# ATmega128.net
KiCad netlist of a schematic drawn in Altium Designer
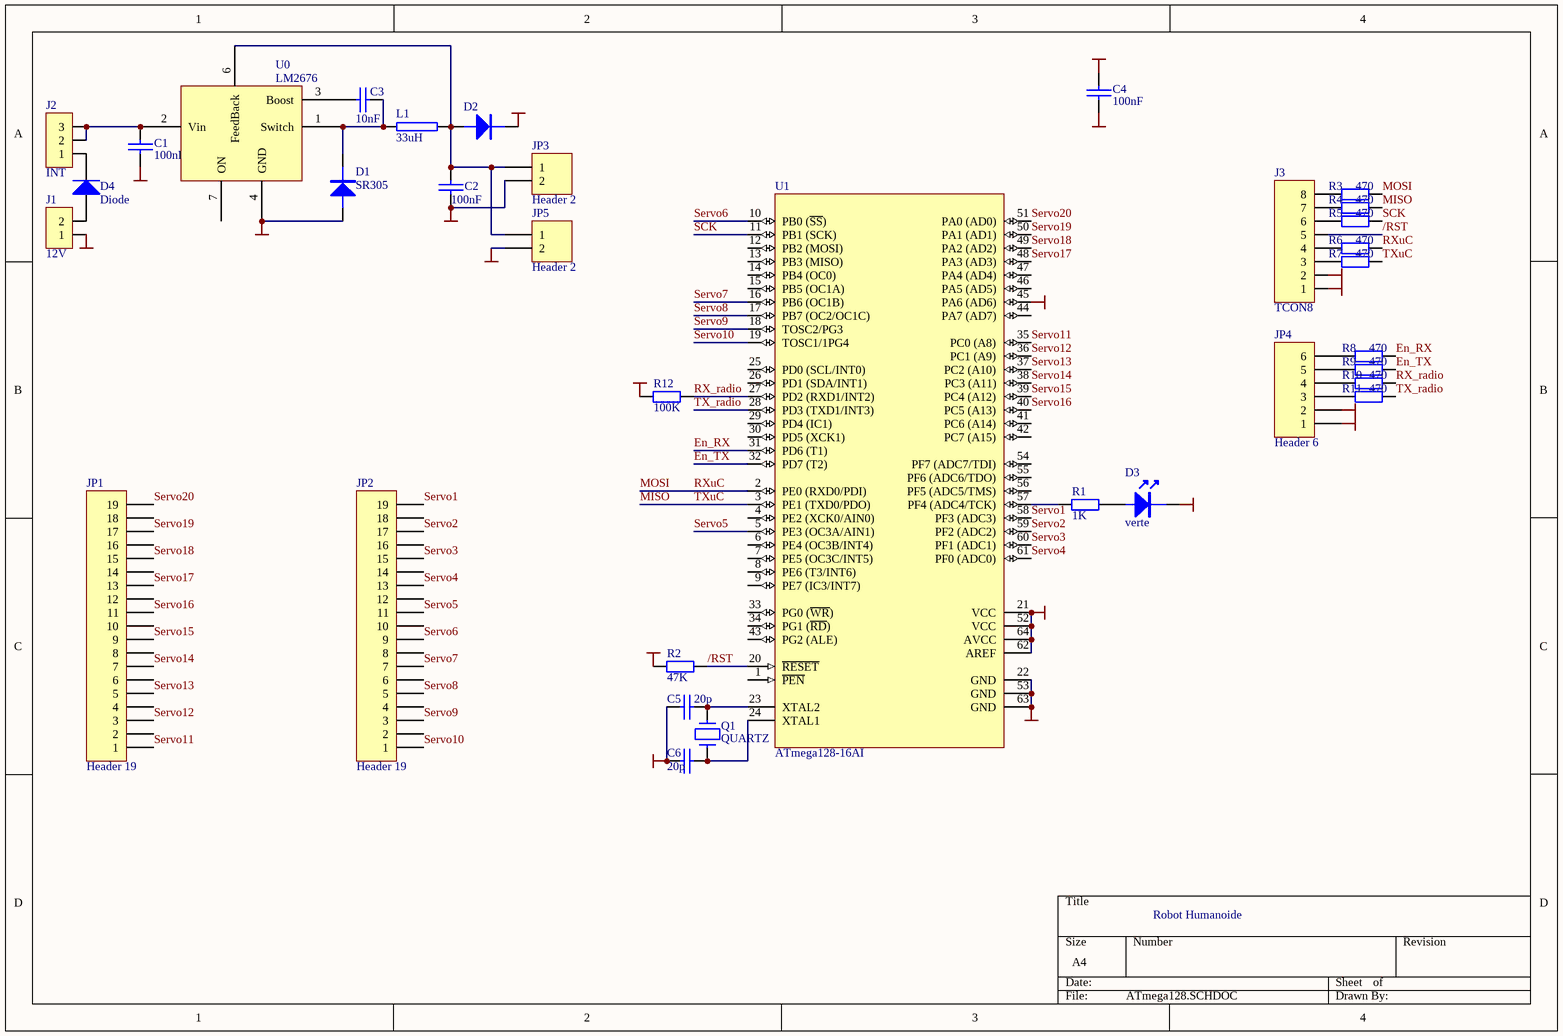
[diagram p0: ATmega128.SCHDOC]

(export (version "E")
  (design (tool "Eeschema 10.0.6"))
  (components
    (comp (ref "C1") (value "100nF") (footprint "0805") (libsource (lib "*") (part "CAP")))
    (comp (ref "C2") (value "100nF") (footprint "0805") (libsource (lib "*") (part "CAP")))
    (comp (ref "C3") (value "10nF") (footprint "0805") (libsource (lib "*") (part "CONDO")))
    (comp (ref "C4") (value "100nF") (footprint "0805") (libsource (lib "*") (part "CAP")))
    (comp (ref "C5") (value "20p") (footprint "0805") (libsource (lib "*") (part "CONDO")))
    (comp (ref "C6") (value "20p") (footprint "0805") (libsource (lib "*") (part "CONDO")))
    (comp (ref "D1") (value "SR305") (footprint "1812") (libsource (lib "*") (part "DIODE")))
    (comp (ref "D2") (value "~") (footprint "1812") (libsource (lib "*") (part "DIODE")))
    (comp (ref "D3") (value "verte") (footprint "0603") (libsource (lib "*") (part "LED")))
    (comp (ref "D4")
      (value "Diode")
      (footprint "DSO-C2/X3.3")
      (description "Default Diode")
      (fields (field (name "PUBLISHER") "Altium Limited"))
      (libsource (lib "Miscellaneous Devices") (part "Diode"))
    )
    (comp (ref "J1") (value "12V") (footprint "CON2") (libsource (lib "*") (part "CON2")))
    (comp (ref "J2") (value "INT") (footprint "TSIP3") (libsource (lib "*") (part "TCON3")))
    (comp (ref "J3") (value "TCON8") (footprint "TSIP8") (libsource (lib "ROB04") (part "TCON8")))
    (comp (ref "JP1")
      (value "Header 19")
      (footprint "HDR1X19")
      (description "Header, 19-Pin")
      (fields (field (name "PUBLISHER") "Altium Limited"))
      (libsource (lib "Miscellaneous Connectors") (part "Header 19"))
    )
    (comp (ref "JP2")
      (value "Header 19")
      (footprint "HDR1X19")
      (description "Header, 19-Pin")
      (fields (field (name "PUBLISHER") "Altium Limited"))
      (libsource (lib "Miscellaneous Connectors") (part "Header 19"))
    )
    (comp (ref "JP3")
      (value "Header 2")
      (footprint "HDR1X2")
      (description "Header, 2-Pin")
      (fields (field (name "PUBLISHER") "Altium Limited"))
      (libsource (lib "Miscellaneous Connectors") (part "Header 2"))
    )
    (comp (ref "JP4")
      (value "Header 6")
      (footprint "TSIP6")
      (description "Header, 6-Pin")
      (fields (field (name "PUBLISHER") "Altium Limited"))
      (libsource (lib "Miscellaneous Connectors") (part "Header 6"))
    )
    (comp (ref "JP5")
      (value "Header 2")
      (footprint "HDR1X2")
      (description "Header, 2-Pin")
      (fields (field (name "PUBLISHER") "Altium Limited"))
      (libsource (lib "Miscellaneous Connectors") (part "Header 2"))
    )
    (comp (ref "L1")
      (value "33uH")
      (footprint "TRES")
      (fields (field (name "PUBLISHER") "*"))
      (libsource (lib "*") (part "RES2"))
    )
    (comp (ref "Q1") (value "QUARTZ") (footprint "XTAL1") (libsource (lib "*") (part "QUARTZ")))
    (comp (ref "R1")
      (value "1K")
      (footprint "0805")
      (description "Resistor")
      (fields (field (name "Comment") "Res2") (field (name "PUBLISHER") "Altium Limited"))
      (libsource (lib "") (part "Res2_1"))
    )
    (comp (ref "R2")
      (value "47K")
      (footprint "0805")
      (description "Resistor")
      (fields (field (name "Comment") "Res2") (field (name "PUBLISHER") "Altium Limited"))
      (libsource (lib "") (part "Res2_1"))
    )
    (comp (ref "R3")
      (value "470")
      (footprint "0805")
      (description "Resistor")
      (fields (field (name "Comment") "Res2") (field (name "PUBLISHER") "Altium Limited"))
      (libsource (lib "Miscellaneous Devices") (part "Res2"))
    )
    (comp (ref "R4")
      (value "470")
      (footprint "0805")
      (description "Resistor")
      (fields (field (name "Comment") "Res2") (field (name "PUBLISHER") "Altium Limited"))
      (libsource (lib "Miscellaneous Devices") (part "Res2"))
    )
    (comp (ref "R5")
      (value "470")
      (footprint "0805")
      (description "Resistor")
      (fields (field (name "Comment") "Res2") (field (name "PUBLISHER") "Altium Limited"))
      (libsource (lib "Miscellaneous Devices") (part "Res2"))
    )
    (comp (ref "R6")
      (value "470")
      (footprint "0805")
      (description "Resistor")
      (fields (field (name "Comment") "Res2") (field (name "PUBLISHER") "Altium Limited"))
      (libsource (lib "Miscellaneous Devices") (part "Res2"))
    )
    (comp (ref "R7")
      (value "470")
      (footprint "0805")
      (description "Resistor")
      (fields (field (name "Comment") "Res2") (field (name "PUBLISHER") "Altium Limited"))
      (libsource (lib "Miscellaneous Devices") (part "Res2"))
    )
    (comp (ref "R8")
      (value "470")
      (footprint "0805")
      (description "Resistor")
      (fields (field (name "Comment") "Res2") (field (name "PUBLISHER") "Altium Limited"))
      (libsource (lib "Miscellaneous Devices") (part "Res2"))
    )
    (comp (ref "R9")
      (value "470")
      (footprint "0805")
      (description "Resistor")
      (fields (field (name "Comment") "Res2") (field (name "PUBLISHER") "Altium Limited"))
      (libsource (lib "Miscellaneous Devices") (part "Res2"))
    )
    (comp (ref "R10")
      (value "470")
      (footprint "0805")
      (description "Resistor")
      (fields (field (name "Comment") "Res2") (field (name "PUBLISHER") "Altium Limited"))
      (libsource (lib "Miscellaneous Devices") (part "Res2"))
    )
    (comp (ref "R11")
      (value "470")
      (footprint "0805")
      (description "Resistor")
      (fields (field (name "Comment") "Res2") (field (name "PUBLISHER") "Altium Limited"))
      (libsource (lib "Miscellaneous Devices") (part "Res2"))
    )
    (comp (ref "R12")
      (value "100K")
      (footprint "0805")
      (description "Resistor")
      (fields (field (name "Comment") "Res2") (field (name "PUBLISHER") "Altium Limited"))
      (libsource (lib "") (part "Res2_1"))
    )
    (comp (ref "U0") (value "LM2676") (footprint "LM2676") (libsource (lib "*") (part "LM2676")))
    (comp (ref "U1")
      (value "ATmega128-16AI")
      (footprint "64A")
      (description "8-Bit AVR Microcontroller with 128K Bytes of In-System Programmable Flash Memory")
      (fields (field (name "PUBLISHER") "Altium Limited"))
      (libsource (lib "Atmel Microcontroller 8-Bit AVR") (part "ATmega128-16AI"))
    )
  )
  (nets
    (net (code "1") (name "/En_RX") (class "Default")
      (node (ref "R8") (pin "2") (pinfunction "2_2") (pintype "passive"))
      (node (ref "U1") (pin "31") (pinfunction "PD6_(T1)_31") (pintype "bidirectional"))
    )
    (net (code "2") (name "/En_TX") (class "Default")
      (node (ref "R9") (pin "2") (pinfunction "2_2") (pintype "passive"))
      (node (ref "U1") (pin "32") (pinfunction "PD7_(T2)_32") (pintype "bidirectional"))
    )
    (net (code "3") (name "/MISO") (class "Default")
      (node (ref "R4") (pin "2") (pinfunction "2_2") (pintype "passive"))
      (node (ref "R7") (pin "2") (pinfunction "2_2") (pintype "passive"))
      (node (ref "U1") (pin "3") (pinfunction "PE1_(TXD0/PDO)_3") (pintype "bidirectional"))
    )
    (net (code "4") (name "/MOSI") (class "Default")
      (node (ref "R3") (pin "2") (pinfunction "2_2") (pintype "passive"))
      (node (ref "R6") (pin "2") (pinfunction "2_2") (pintype "passive"))
      (node (ref "U1") (pin "2") (pinfunction "PE0_(RXD0/PDI)_2") (pintype "bidirectional"))
    )
    (net (code "5") (name "/RX_radio") (class "Default")
      (node (ref "R10") (pin "2") (pinfunction "2_2") (pintype "passive"))
      (node (ref "R12") (pin "1") (pinfunction "1_1") (pintype "passive"))
      (node (ref "U1") (pin "27") (pinfunction "PD2_(RXD1/INT2)_27") (pintype "bidirectional"))
    )
    (net (code "6") (name "/SCK") (class "Default")
      (node (ref "R5") (pin "2") (pinfunction "2_2") (pintype "passive"))
      (node (ref "U1") (pin "11") (pinfunction "PB1_(SCK)_11") (pintype "bidirectional"))
    )
    (net (code "7") (name "/Servo1") (class "Default")
      (node (ref "JP2") (pin "19") (pinfunction "19_19") (pintype "passive"))
      (node (ref "U1") (pin "58") (pinfunction "PF3_(ADC3)_58") (pintype "bidirectional"))
    )
    (net (code "8") (name "/Servo2") (class "Default")
      (node (ref "JP2") (pin "17") (pinfunction "17_17") (pintype "passive"))
      (node (ref "U1") (pin "59") (pinfunction "PF2_(ADC2)_59") (pintype "bidirectional"))
    )
    (net (code "9") (name "/Servo3") (class "Default")
      (node (ref "JP2") (pin "15") (pinfunction "15_15") (pintype "passive"))
      (node (ref "U1") (pin "60") (pinfunction "PF1_(ADC1)_60") (pintype "bidirectional"))
    )
    (net (code "10") (name "/Servo4") (class "Default")
      (node (ref "JP2") (pin "13") (pinfunction "13_13") (pintype "passive"))
      (node (ref "U1") (pin "61") (pinfunction "PF0_(ADC0)_61") (pintype "bidirectional"))
    )
    (net (code "11") (name "/Servo5") (class "Default")
      (node (ref "JP2") (pin "11") (pinfunction "11_11") (pintype "passive"))
      (node (ref "U1") (pin "5") (pinfunction "PE3_(OC3A/AIN1)_5") (pintype "bidirectional"))
    )
    (net (code "12") (name "/Servo6") (class "Default")
      (node (ref "JP2") (pin "9") (pinfunction "9_9") (pintype "passive"))
      (node (ref "U1") (pin "10") (pinfunction "PB0_(~{SS})_10") (pintype "bidirectional"))
    )
    (net (code "13") (name "/Servo7") (class "Default")
      (node (ref "JP2") (pin "7") (pinfunction "7_7") (pintype "passive"))
      (node (ref "U1") (pin "16") (pinfunction "PB6_(OC1B)_16") (pintype "bidirectional"))
    )
    (net (code "14") (name "/Servo8") (class "Default")
      (node (ref "JP2") (pin "5") (pinfunction "5_5") (pintype "passive"))
      (node (ref "U1") (pin "17") (pinfunction "PB7_(OC2/OC1C)_17") (pintype "bidirectional"))
    )
    (net (code "15") (name "/Servo9") (class "Default")
      (node (ref "JP2") (pin "3") (pinfunction "3_3") (pintype "passive"))
      (node (ref "U1") (pin "18") (pinfunction "TOSC2/PG3_18") (pintype "bidirectional"))
    )
    (net (code "16") (name "/Servo10") (class "Default")
      (node (ref "JP2") (pin "1") (pinfunction "1_1") (pintype "passive"))
      (node (ref "U1") (pin "19") (pinfunction "TOSC1/1PG4_19") (pintype "bidirectional"))
    )
    (net (code "17") (name "/Servo11") (class "Default")
      (node (ref "JP1") (pin "1") (pinfunction "1_1") (pintype "passive"))
      (node (ref "U1") (pin "35") (pinfunction "PC0_(A8)_35") (pintype "bidirectional"))
    )
    (net (code "18") (name "/Servo12") (class "Default")
      (node (ref "JP1") (pin "3") (pinfunction "3_3") (pintype "passive"))
      (node (ref "U1") (pin "36") (pinfunction "PC1_(A9)_36") (pintype "bidirectional"))
    )
    (net (code "19") (name "/Servo13") (class "Default")
      (node (ref "JP1") (pin "5") (pinfunction "5_5") (pintype "passive"))
      (node (ref "U1") (pin "37") (pinfunction "PC2_(A10)_37") (pintype "bidirectional"))
    )
    (net (code "20") (name "/Servo14") (class "Default")
      (node (ref "JP1") (pin "7") (pinfunction "7_7") (pintype "passive"))
      (node (ref "U1") (pin "38") (pinfunction "PC3_(A11)_38") (pintype "bidirectional"))
    )
    (net (code "21") (name "/Servo15") (class "Default")
      (node (ref "JP1") (pin "9") (pinfunction "9_9") (pintype "passive"))
      (node (ref "U1") (pin "39") (pinfunction "PC4_(A12)_39") (pintype "bidirectional"))
    )
    (net (code "22") (name "/Servo16") (class "Default")
      (node (ref "JP1") (pin "11") (pinfunction "11_11") (pintype "passive"))
      (node (ref "U1") (pin "40") (pinfunction "PC5_(A13)_40") (pintype "bidirectional"))
    )
    (net (code "23") (name "/Servo17") (class "Default")
      (node (ref "JP1") (pin "13") (pinfunction "13_13") (pintype "passive"))
      (node (ref "U1") (pin "48") (pinfunction "PA3_(AD3)_48") (pintype "bidirectional"))
    )
    (net (code "24") (name "/Servo18") (class "Default")
      (node (ref "JP1") (pin "15") (pinfunction "15_15") (pintype "passive"))
      (node (ref "U1") (pin "49") (pinfunction "PA2_(AD2)_49") (pintype "bidirectional"))
    )
    (net (code "25") (name "/Servo19") (class "Default")
      (node (ref "JP1") (pin "17") (pinfunction "17_17") (pintype "passive"))
      (node (ref "U1") (pin "50") (pinfunction "PA1_(AD1)_50") (pintype "bidirectional"))
    )
    (net (code "26") (name "/Servo20") (class "Default")
      (node (ref "JP1") (pin "19") (pinfunction "19_19") (pintype "passive"))
      (node (ref "U1") (pin "51") (pinfunction "PA0_(AD0)_51") (pintype "bidirectional"))
    )
    (net (code "27") (name "/TX_radio") (class "Default")
      (node (ref "R11") (pin "2") (pinfunction "2_2") (pintype "passive"))
      (node (ref "U1") (pin "28") (pinfunction "PD3_(TXD1/INT3)_28") (pintype "bidirectional"))
    )
    (net (code "28") (name "/{slash}RST") (class "Default")
      (node (ref "J3") (pin "5") (pinfunction "5_5") (pintype "passive"))
      (node (ref "R2") (pin "1") (pinfunction "1_1") (pintype "passive"))
      (node (ref "U1") (pin "20") (pinfunction "~{RESET}_20") (pintype "input"))
    )
    (net (code "29") (name "5V") (class "Default")
      (node (ref "C4") (pin "2") (pintype "passive"))
      (node (ref "D2") (pin "1") (pintype "passive"))
      (node (ref "J3") (pin "1") (pinfunction "1_1") (pintype "passive"))
      (node (ref "JP4") (pin "1") (pinfunction "1_1") (pintype "passive"))
      (node (ref "R12") (pin "2") (pinfunction "2_2") (pintype "passive"))
      (node (ref "R2") (pin "2") (pinfunction "2_2") (pintype "passive"))
      (node (ref "U1") (pin "21") (pinfunction "VCC_21") (pintype "power_in"))
      (node (ref "U1") (pin "52") (pinfunction "VCC_52") (pintype "power_in"))
      (node (ref "U1") (pin "62") (pinfunction "AREF_62") (pintype "passive"))
      (node (ref "U1") (pin "64") (pinfunction "AVCC_64") (pintype "power_in"))
    )
    (net (code "30") (name "GND") (class "Default")
      (node (ref "C1") (pin "1") (pintype "passive"))
      (node (ref "C2") (pin "1") (pintype "passive"))
      (node (ref "C4") (pin "1") (pintype "passive"))
      (node (ref "C5") (pin "2") (pintype "passive"))
      (node (ref "C6") (pin "2") (pintype "passive"))
      (node (ref "D1") (pin "2") (pintype "passive"))
      (node (ref "D3") (pin "2") (pintype "passive"))
      (node (ref "J1") (pin "1") (pinfunction "1_1") (pintype "passive"))
      (node (ref "J3") (pin "2") (pinfunction "2_2") (pintype "passive"))
      (node (ref "JP3") (pin "2") (pinfunction "2_2") (pintype "passive"))
      (node (ref "JP4") (pin "2") (pinfunction "2_2") (pintype "passive"))
      (node (ref "JP5") (pin "2") (pinfunction "2_2") (pintype "passive"))
      (node (ref "U0") (pin "4") (pinfunction "GND_4") (pintype "passive"))
      (node (ref "U1") (pin "22") (pinfunction "GND_22") (pintype "power_in"))
      (node (ref "U1") (pin "45") (pinfunction "PA6_(AD6)_45") (pintype "bidirectional"))
      (node (ref "U1") (pin "53") (pinfunction "GND_53") (pintype "power_in"))
      (node (ref "U1") (pin "63") (pinfunction "GND_63") (pintype "power_in"))
    )
    (net (code "31") (name "Net-(D3-Pad1)") (class "Default")
      (node (ref "D3") (pin "1") (pintype "passive"))
      (node (ref "R1") (pin "1") (pinfunction "1_1") (pintype "passive"))
    )
    (net (code "32") (name "Net-(D4-A)") (class "Default")
      (node (ref "D4") (pin "1") (pinfunction "A_1") (pintype "passive"))
      (node (ref "J1") (pin "2") (pinfunction "2_2") (pintype "passive"))
    )
    (net (code "33") (name "Net-(D4-K)") (class "Default")
      (node (ref "D4") (pin "2") (pinfunction "K_2") (pintype "passive"))
      (node (ref "J2") (pin "1") (pinfunction "1_1") (pintype "passive"))
    )
    (net (code "34") (name "Net-(J3-Pad3)") (class "Default")
      (node (ref "J3") (pin "3") (pinfunction "3_3") (pintype "passive"))
      (node (ref "R7") (pin "1") (pinfunction "1_1") (pintype "passive"))
    )
    (net (code "35") (name "Net-(J3-Pad4)") (class "Default")
      (node (ref "J3") (pin "4") (pinfunction "4_4") (pintype "passive"))
      (node (ref "R6") (pin "1") (pinfunction "1_1") (pintype "passive"))
    )
    (net (code "36") (name "Net-(J3-Pad6)") (class "Default")
      (node (ref "J3") (pin "6") (pinfunction "6_6") (pintype "passive"))
      (node (ref "R5") (pin "1") (pinfunction "1_1") (pintype "passive"))
    )
    (net (code "37") (name "Net-(J3-Pad7)") (class "Default")
      (node (ref "J3") (pin "7") (pinfunction "7_7") (pintype "passive"))
      (node (ref "R4") (pin "1") (pinfunction "1_1") (pintype "passive"))
    )
    (net (code "38") (name "Net-(J3-Pad8)") (class "Default")
      (node (ref "J3") (pin "8") (pinfunction "8_8") (pintype "passive"))
      (node (ref "R3") (pin "1") (pinfunction "1_1") (pintype "passive"))
    )
    (net (code "39") (name "Net-(JP4-Pad3)") (class "Default")
      (node (ref "JP4") (pin "3") (pinfunction "3_3") (pintype "passive"))
      (node (ref "R11") (pin "1") (pinfunction "1_1") (pintype "passive"))
    )
    (net (code "40") (name "Net-(JP4-Pad4)") (class "Default")
      (node (ref "JP4") (pin "4") (pinfunction "4_4") (pintype "passive"))
      (node (ref "R10") (pin "1") (pinfunction "1_1") (pintype "passive"))
    )
    (net (code "41") (name "Net-(JP4-Pad5)") (class "Default")
      (node (ref "JP4") (pin "5") (pinfunction "5_5") (pintype "passive"))
      (node (ref "R9") (pin "1") (pinfunction "1_1") (pintype "passive"))
    )
    (net (code "42") (name "Net-(JP4-Pad6)") (class "Default")
      (node (ref "JP4") (pin "6") (pinfunction "6_6") (pintype "passive"))
      (node (ref "R8") (pin "1") (pinfunction "1_1") (pintype "passive"))
    )
    (net (code "43") (name "Net-(U0-Boost)") (class "Default")
      (node (ref "C3") (pin "1") (pintype "passive"))
      (node (ref "U0") (pin "3") (pinfunction "Boost_3") (pintype "passive"))
    )
    (net (code "44") (name "Net-(U0-FeedBack)") (class "Default")
      (node (ref "C2") (pin "2") (pintype "passive"))
      (node (ref "D2") (pin "2") (pintype "passive"))
      (node (ref "JP3") (pin "1") (pinfunction "1_1") (pintype "passive"))
      (node (ref "JP5") (pin "1") (pinfunction "1_1") (pintype "passive"))
      (node (ref "L1") (pin "2") (pintype "passive"))
      (node (ref "U0") (pin "6") (pinfunction "FeedBack_6") (pintype "passive"))
    )
    (net (code "45") (name "Net-(U0-Switch)") (class "Default")
      (node (ref "C3") (pin "2") (pintype "passive"))
      (node (ref "D1") (pin "1") (pintype "passive"))
      (node (ref "L1") (pin "1") (pintype "passive"))
      (node (ref "U0") (pin "1") (pinfunction "Switch_1") (pintype "passive"))
    )
    (net (code "46") (name "Net-(U0-Vin)") (class "Default")
      (node (ref "C1") (pin "2") (pintype "passive"))
      (node (ref "J2") (pin "2") (pinfunction "2_2") (pintype "passive"))
      (node (ref "J2") (pin "3") (pinfunction "3_3") (pintype "passive"))
      (node (ref "U0") (pin "2") (pinfunction "Vin_2") (pintype "passive"))
    )
    (net (code "47") (name "Net-(U1-PF4_(ADC4{slash}TCK))") (class "Default")
      (node (ref "R1") (pin "2") (pinfunction "2_2") (pintype "passive"))
      (node (ref "U1") (pin "57") (pinfunction "PF4_(ADC4/TCK)_57") (pintype "bidirectional"))
    )
    (net (code "48") (name "Net-(U1-XTAL1)") (class "Default")
      (node (ref "C6") (pin "1") (pintype "passive"))
      (node (ref "Q1") (pin "2") (pintype "passive"))
      (node (ref "U1") (pin "24") (pinfunction "XTAL1_24") (pintype "passive"))
    )
    (net (code "49") (name "Net-(U1-XTAL2)") (class "Default")
      (node (ref "C5") (pin "1") (pintype "passive"))
      (node (ref "Q1") (pin "1") (pintype "passive"))
      (node (ref "U1") (pin "23") (pinfunction "XTAL2_23") (pintype "passive"))
    )
    (net (code "50") (name "unconnected-(JP1-Pad2)") (class "Default")
      (node (ref "JP1") (pin "2") (pinfunction "2_2") (pintype "passive"))
    )
    (net (code "51") (name "unconnected-(JP1-Pad4)") (class "Default")
      (node (ref "JP1") (pin "4") (pinfunction "4_4") (pintype "passive"))
    )
    (net (code "52") (name "unconnected-(JP1-Pad6)") (class "Default")
      (node (ref "JP1") (pin "6") (pinfunction "6_6") (pintype "passive"))
    )
    (net (code "53") (name "unconnected-(JP1-Pad8)") (class "Default")
      (node (ref "JP1") (pin "8") (pinfunction "8_8") (pintype "passive"))
    )
    (net (code "54") (name "unconnected-(JP1-Pad10)") (class "Default")
      (node (ref "JP1") (pin "10") (pinfunction "10_10") (pintype "passive"))
    )
    (net (code "55") (name "unconnected-(JP1-Pad12)") (class "Default")
      (node (ref "JP1") (pin "12") (pinfunction "12_12") (pintype "passive"))
    )
    (net (code "56") (name "unconnected-(JP1-Pad14)") (class "Default")
      (node (ref "JP1") (pin "14") (pinfunction "14_14") (pintype "passive"))
    )
    (net (code "57") (name "unconnected-(JP1-Pad16)") (class "Default")
      (node (ref "JP1") (pin "16") (pinfunction "16_16") (pintype "passive"))
    )
    (net (code "58") (name "unconnected-(JP1-Pad18)") (class "Default")
      (node (ref "JP1") (pin "18") (pinfunction "18_18") (pintype "passive"))
    )
    (net (code "59") (name "unconnected-(JP2-Pad2)") (class "Default")
      (node (ref "JP2") (pin "2") (pinfunction "2_2") (pintype "passive"))
    )
    (net (code "60") (name "unconnected-(JP2-Pad4)") (class "Default")
      (node (ref "JP2") (pin "4") (pinfunction "4_4") (pintype "passive"))
    )
    (net (code "61") (name "unconnected-(JP2-Pad6)") (class "Default")
      (node (ref "JP2") (pin "6") (pinfunction "6_6") (pintype "passive"))
    )
    (net (code "62") (name "unconnected-(JP2-Pad8)") (class "Default")
      (node (ref "JP2") (pin "8") (pinfunction "8_8") (pintype "passive"))
    )
    (net (code "63") (name "unconnected-(JP2-Pad10)") (class "Default")
      (node (ref "JP2") (pin "10") (pinfunction "10_10") (pintype "passive"))
    )
    (net (code "64") (name "unconnected-(JP2-Pad12)") (class "Default")
      (node (ref "JP2") (pin "12") (pinfunction "12_12") (pintype "passive"))
    )
    (net (code "65") (name "unconnected-(JP2-Pad14)") (class "Default")
      (node (ref "JP2") (pin "14") (pinfunction "14_14") (pintype "passive"))
    )
    (net (code "66") (name "unconnected-(JP2-Pad16)") (class "Default")
      (node (ref "JP2") (pin "16") (pinfunction "16_16") (pintype "passive"))
    )
    (net (code "67") (name "unconnected-(JP2-Pad18)") (class "Default")
      (node (ref "JP2") (pin "18") (pinfunction "18_18") (pintype "passive"))
    )
    (net (code "68") (name "unconnected-(U0-ON-Pad7)") (class "Default")
      (node (ref "U0") (pin "7") (pinfunction "ON_7") (pintype "passive"))
    )
    (net (code "69") (name "unconnected-(U1-PA4_(AD4)-Pad47)") (class "Default")
      (node (ref "U1") (pin "47") (pinfunction "PA4_(AD4)_47") (pintype "bidirectional"))
    )
    (net (code "70") (name "unconnected-(U1-PA5_(AD5)-Pad46)") (class "Default")
      (node (ref "U1") (pin "46") (pinfunction "PA5_(AD5)_46") (pintype "bidirectional"))
    )
    (net (code "71") (name "unconnected-(U1-PA7_(AD7)-Pad44)") (class "Default")
      (node (ref "U1") (pin "44") (pinfunction "PA7_(AD7)_44") (pintype "bidirectional"))
    )
    (net (code "72") (name "unconnected-(U1-PB2_(MOSI)-Pad12)") (class "Default")
      (node (ref "U1") (pin "12") (pinfunction "PB2_(MOSI)_12") (pintype "bidirectional"))
    )
    (net (code "73") (name "unconnected-(U1-PB3_(MISO)-Pad13)") (class "Default")
      (node (ref "U1") (pin "13") (pinfunction "PB3_(MISO)_13") (pintype "bidirectional"))
    )
    (net (code "74") (name "unconnected-(U1-PB4_(OC0)-Pad14)") (class "Default")
      (node (ref "U1") (pin "14") (pinfunction "PB4_(OC0)_14") (pintype "bidirectional"))
    )
    (net (code "75") (name "unconnected-(U1-PB5_(OC1A)-Pad15)") (class "Default")
      (node (ref "U1") (pin "15") (pinfunction "PB5_(OC1A)_15") (pintype "bidirectional"))
    )
    (net (code "76") (name "unconnected-(U1-PC6_(A14)-Pad41)") (class "Default")
      (node (ref "U1") (pin "41") (pinfunction "PC6_(A14)_41") (pintype "bidirectional"))
    )
    (net (code "77") (name "unconnected-(U1-PC7_(A15)-Pad42)") (class "Default")
      (node (ref "U1") (pin "42") (pinfunction "PC7_(A15)_42") (pintype "bidirectional"))
    )
    (net (code "78") (name "unconnected-(U1-PD0_(SCL{slash}INT0)-Pad25)") (class "Default")
      (node (ref "U1") (pin "25") (pinfunction "PD0_(SCL/INT0)_25") (pintype "bidirectional"))
    )
    (net (code "79") (name "unconnected-(U1-PD1_(SDA{slash}INT1)-Pad26)") (class "Default")
      (node (ref "U1") (pin "26") (pinfunction "PD1_(SDA/INT1)_26") (pintype "bidirectional"))
    )
    (net (code "80") (name "unconnected-(U1-PD4_(IC1)-Pad29)") (class "Default")
      (node (ref "U1") (pin "29") (pinfunction "PD4_(IC1)_29") (pintype "bidirectional"))
    )
    (net (code "81") (name "unconnected-(U1-PD5_(XCK1)-Pad30)") (class "Default")
      (node (ref "U1") (pin "30") (pinfunction "PD5_(XCK1)_30") (pintype "bidirectional"))
    )
    (net (code "82") (name "unconnected-(U1-PE2_(XCK0{slash}AIN0)-Pad4)") (class "Default")
      (node (ref "U1") (pin "4") (pinfunction "PE2_(XCK0/AIN0)_4") (pintype "bidirectional"))
    )
    (net (code "83") (name "unconnected-(U1-PE4_(OC3B{slash}INT4)-Pad6)") (class "Default")
      (node (ref "U1") (pin "6") (pinfunction "PE4_(OC3B/INT4)_6") (pintype "bidirectional"))
    )
    (net (code "84") (name "unconnected-(U1-PE5_(OC3C{slash}INT5)-Pad7)") (class "Default")
      (node (ref "U1") (pin "7") (pinfunction "PE5_(OC3C/INT5)_7") (pintype "bidirectional"))
    )
    (net (code "85") (name "unconnected-(U1-PE6_(T3{slash}INT6)-Pad8)") (class "Default")
      (node (ref "U1") (pin "8") (pinfunction "PE6_(T3/INT6)_8") (pintype "bidirectional"))
    )
    (net (code "86") (name "unconnected-(U1-PE7_(IC3{slash}INT7)-Pad9)") (class "Default")
      (node (ref "U1") (pin "9") (pinfunction "PE7_(IC3/INT7)_9") (pintype "bidirectional"))
    )
    (net (code "87") (name "unconnected-(U1-PF5_(ADC5{slash}TMS)-Pad56)") (class "Default")
      (node (ref "U1") (pin "56") (pinfunction "PF5_(ADC5/TMS)_56") (pintype "bidirectional"))
    )
    (net (code "88") (name "unconnected-(U1-PF6_(ADC6{slash}TDO)-Pad55)") (class "Default")
      (node (ref "U1") (pin "55") (pinfunction "PF6_(ADC6/TDO)_55") (pintype "bidirectional"))
    )
    (net (code "89") (name "unconnected-(U1-PF7_(ADC7{slash}TDI)-Pad54)") (class "Default")
      (node (ref "U1") (pin "54") (pinfunction "PF7_(ADC7/TDI)_54") (pintype "bidirectional"))
    )
    (net (code "90") (name "unconnected-(U1-PG0_(~{WR})-Pad33)") (class "Default")
      (node (ref "U1") (pin "33") (pinfunction "PG0_(~{WR})_33") (pintype "bidirectional"))
    )
    (net (code "91") (name "unconnected-(U1-PG1_(~{RD})-Pad34)") (class "Default")
      (node (ref "U1") (pin "34") (pinfunction "PG1_(~{RD})_34") (pintype "bidirectional"))
    )
    (net (code "92") (name "unconnected-(U1-PG2_(ALE)-Pad43)") (class "Default")
      (node (ref "U1") (pin "43") (pinfunction "PG2_(ALE)_43") (pintype "bidirectional"))
    )
    (net (code "93") (name "unconnected-(U1-~{PEN}-Pad1)") (class "Default")
      (node (ref "U1") (pin "1") (pinfunction "~{PEN}_1") (pintype "input"))
    )
  )
)
